# v1_4_button.net
KiCad netlist of a schematic drawn in EAGLE
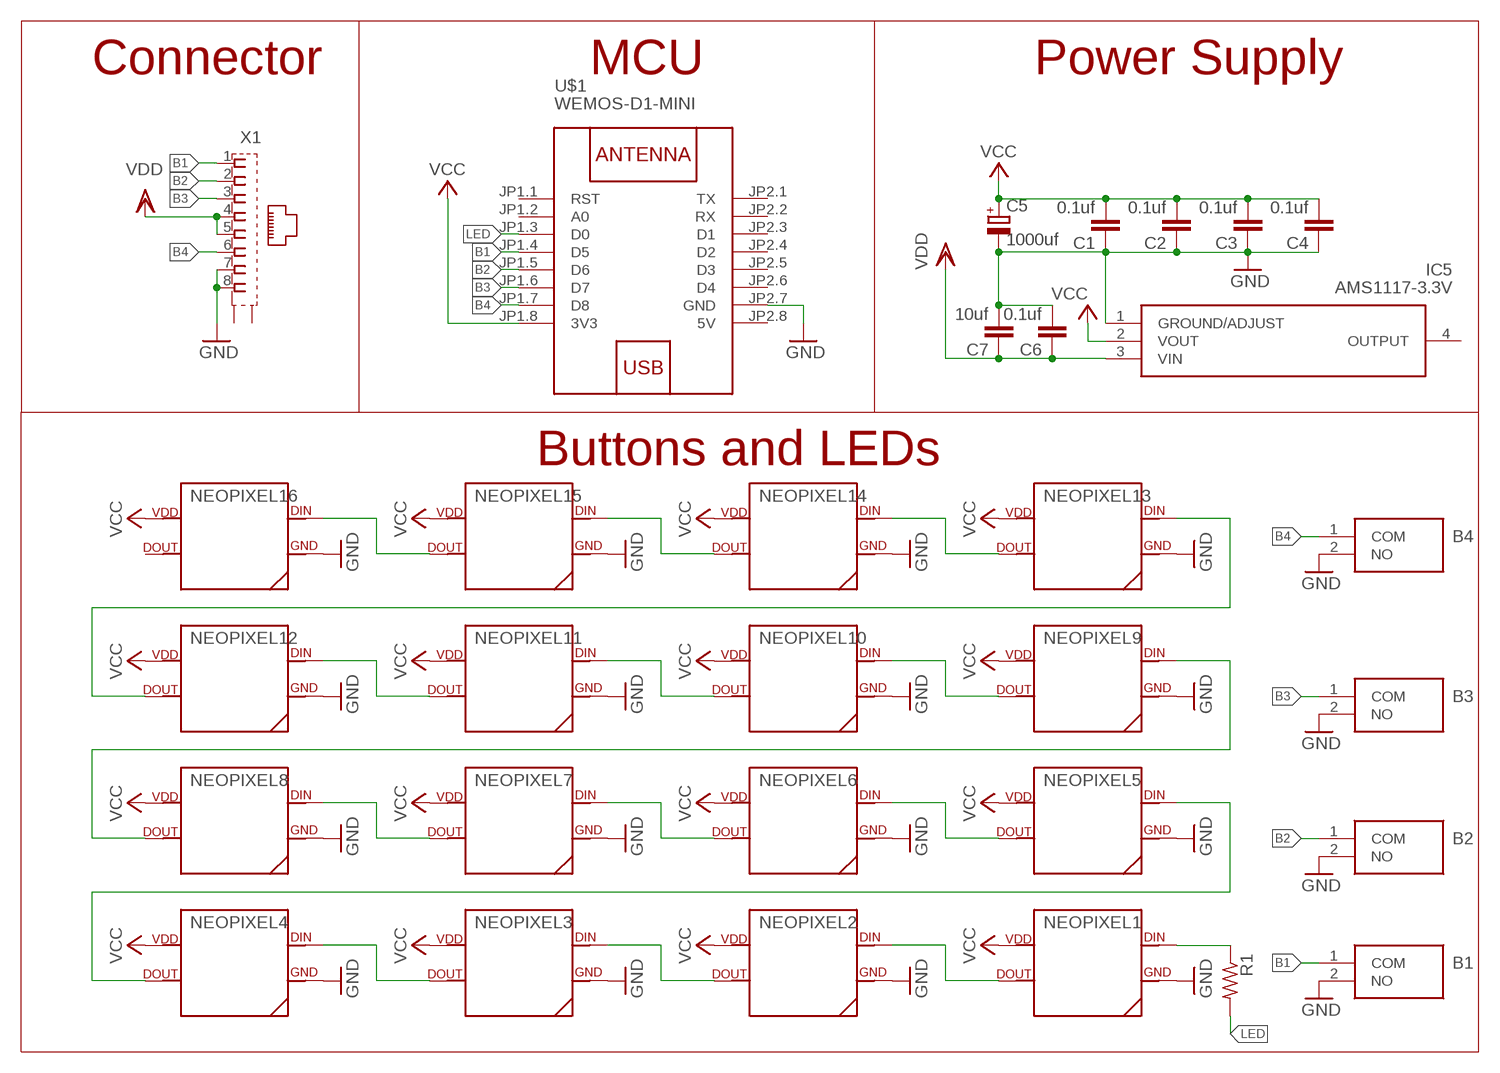
[diagram p0: schematic, sheet 1]

(export (version "E")
  (design (tool "Eeschema 10.0.6"))
  (components
    (comp (ref "B1")
      (value "PTS636_SM25F_SMTR_LFS")
      (footprint "eagle-import:PTS636SM25FSMTRLFS")
      (fields
        (field (name "ARROW_PART_NUMBER") "PTS636 SM25F SMTR LFS")
        (field (name "MOUSER_PART_NUMBER") "611-PTS636SM25FSMTRL")
      )
      (libsource (lib "eagle-import") (part "PTS636_SM25F_SMTR_LFS"))
    )
    (comp (ref "B2")
      (value "PTS636_SM25F_SMTR_LFS")
      (footprint "eagle-import:PTS636SM25FSMTRLFS")
      (fields
        (field (name "ARROW_PART_NUMBER") "PTS636 SM25F SMTR LFS")
        (field (name "MOUSER_PART_NUMBER") "611-PTS636SM25FSMTRL")
      )
      (libsource (lib "eagle-import") (part "PTS636_SM25F_SMTR_LFS"))
    )
    (comp (ref "B3")
      (value "PTS636_SM25F_SMTR_LFS")
      (footprint "eagle-import:PTS636SM25FSMTRLFS")
      (fields
        (field (name "ARROW_PART_NUMBER") "PTS636 SM25F SMTR LFS")
        (field (name "MOUSER_PART_NUMBER") "611-PTS636SM25FSMTRL")
      )
      (libsource (lib "eagle-import") (part "PTS636_SM25F_SMTR_LFS"))
    )
    (comp (ref "B4")
      (value "PTS636_SM25F_SMTR_LFS")
      (footprint "eagle-import:PTS636SM25FSMTRLFS")
      (fields
        (field (name "ARROW_PART_NUMBER") "PTS636 SM25F SMTR LFS")
        (field (name "MOUSER_PART_NUMBER") "611-PTS636SM25FSMTRL")
      )
      (libsource (lib "eagle-import") (part "PTS636_SM25F_SMTR_LFS"))
    )
    (comp (ref "C1")
      (value "0.1uf")
      (footprint "eagle-import:C0603")
      (libsource (lib "eagle-import") (part "C-EUC0603"))
    )
    (comp (ref "C2")
      (value "0.1uf")
      (footprint "eagle-import:C0603")
      (libsource (lib "eagle-import") (part "C-EUC0603"))
    )
    (comp (ref "C3")
      (value "0.1uf")
      (footprint "eagle-import:C0603")
      (libsource (lib "eagle-import") (part "C-EUC0603"))
    )
    (comp (ref "C4")
      (value "0.1uf")
      (footprint "eagle-import:C0603")
      (libsource (lib "eagle-import") (part "C-EUC0603"))
    )
    (comp (ref "C5")
      (value "1000uf")
      (footprint "eagle-import:UD-6,3X7,7_NICHICON")
      (libsource (lib "eagle-import") (part "CPOL-EUUD-6,3X7,7"))
    )
    (comp (ref "C6")
      (value "0.1uf")
      (footprint "eagle-import:C0603")
      (libsource (lib "eagle-import") (part "C-EUC0603"))
    )
    (comp (ref "C7")
      (value "10uf")
      (footprint "eagle-import:C0603")
      (libsource (lib "eagle-import") (part "C-EUC0603"))
    )
    (comp (ref "IC5")
      (value "AMS1117-3.3V")
      (footprint "eagle-import:SOT229P700X180-4N")
      (fields (field (name "MANUFACTURER_PART_NUMBER") "ams1117-3.3v"))
      (libsource (lib "eagle-import") (part "AMS1117-3.3V"))
    )
    (comp (ref "NEOPIXEL1")
      (value "SK6812NEOPIXEL5050")
      (footprint "eagle-import:SK6812")
      (libsource (lib "eagle-import") (part "SK68125050NEOPIXEL"))
    )
    (comp (ref "NEOPIXEL2")
      (value "SK6812NEOPIXEL5050")
      (footprint "eagle-import:SK6812")
      (libsource (lib "eagle-import") (part "SK68125050NEOPIXEL"))
    )
    (comp (ref "NEOPIXEL3")
      (value "SK6812NEOPIXEL5050")
      (footprint "eagle-import:SK6812")
      (libsource (lib "eagle-import") (part "SK68125050NEOPIXEL"))
    )
    (comp (ref "NEOPIXEL4")
      (value "SK6812NEOPIXEL5050")
      (footprint "eagle-import:SK6812")
      (libsource (lib "eagle-import") (part "SK68125050NEOPIXEL"))
    )
    (comp (ref "NEOPIXEL5")
      (value "SK6812NEOPIXEL5050")
      (footprint "eagle-import:SK6812")
      (libsource (lib "eagle-import") (part "SK68125050NEOPIXEL"))
    )
    (comp (ref "NEOPIXEL6")
      (value "SK6812NEOPIXEL5050")
      (footprint "eagle-import:SK6812")
      (libsource (lib "eagle-import") (part "SK68125050NEOPIXEL"))
    )
    (comp (ref "NEOPIXEL7")
      (value "SK6812NEOPIXEL5050")
      (footprint "eagle-import:SK6812")
      (libsource (lib "eagle-import") (part "SK68125050NEOPIXEL"))
    )
    (comp (ref "NEOPIXEL8")
      (value "SK6812NEOPIXEL5050")
      (footprint "eagle-import:SK6812")
      (libsource (lib "eagle-import") (part "SK68125050NEOPIXEL"))
    )
    (comp (ref "NEOPIXEL9")
      (value "SK6812NEOPIXEL5050")
      (footprint "eagle-import:SK6812")
      (libsource (lib "eagle-import") (part "SK68125050NEOPIXEL"))
    )
    (comp (ref "NEOPIXEL10")
      (value "SK6812NEOPIXEL5050")
      (footprint "eagle-import:SK6812")
      (libsource (lib "eagle-import") (part "SK68125050NEOPIXEL"))
    )
    (comp (ref "NEOPIXEL11")
      (value "SK6812NEOPIXEL5050")
      (footprint "eagle-import:SK6812")
      (libsource (lib "eagle-import") (part "SK68125050NEOPIXEL"))
    )
    (comp (ref "NEOPIXEL12")
      (value "SK6812NEOPIXEL5050")
      (footprint "eagle-import:SK6812")
      (libsource (lib "eagle-import") (part "SK68125050NEOPIXEL"))
    )
    (comp (ref "NEOPIXEL13")
      (value "SK6812NEOPIXEL5050")
      (footprint "eagle-import:SK6812")
      (libsource (lib "eagle-import") (part "SK68125050NEOPIXEL"))
    )
    (comp (ref "NEOPIXEL14")
      (value "SK6812NEOPIXEL5050")
      (footprint "eagle-import:SK6812")
      (libsource (lib "eagle-import") (part "SK68125050NEOPIXEL"))
    )
    (comp (ref "NEOPIXEL15")
      (value "SK6812NEOPIXEL5050")
      (footprint "eagle-import:SK6812")
      (libsource (lib "eagle-import") (part "SK68125050NEOPIXEL"))
    )
    (comp (ref "NEOPIXEL16")
      (value "SK6812NEOPIXEL5050")
      (footprint "eagle-import:SK6812")
      (libsource (lib "eagle-import") (part "SK68125050NEOPIXEL"))
    )
    (comp (ref "R1")
      (value "R-US_R0603")
      (footprint "eagle-import:R0603")
      (libsource (lib "eagle-import") (part "R-US_R0603"))
    )
    (comp (ref "U$1")
      (value "WEMOS-D1-MINI")
      (footprint "eagle-import:WEMOS-D1-MINI")
      (libsource (lib "eagle-import") (part "WEMOS-D1-MINI"))
    )
    (comp (ref "X1")
      (value "0446200002")
      (footprint "eagle-import:0446200002")
      (fields (field (name "MF") "MOLEX"))
      (libsource (lib "eagle-import") (part "0446200002"))
    )
  )
  (nets
    (net (code "1") (name "/5V") (class "Default")
      (node (ref "U$1") (pin "JP2.8") (pinfunction "5V_JP2.8") (pintype "power_in"))
    )
    (net (code "2") (name "B1") (class "Default")
      (node (ref "B1") (pin "1") (pinfunction "COM_1") (pintype "bidirectional"))
      (node (ref "U$1") (pin "JP1.4") (pinfunction "D5_JP1.4") (pintype "bidirectional"))
      (node (ref "X1") (pin "1") (pinfunction "1_1") (pintype "passive"))
    )
    (net (code "3") (name "B2") (class "Default")
      (node (ref "B2") (pin "1") (pinfunction "COM_1") (pintype "bidirectional"))
      (node (ref "U$1") (pin "JP1.5") (pinfunction "D6_JP1.5") (pintype "bidirectional"))
      (node (ref "X1") (pin "2") (pinfunction "2_2") (pintype "passive"))
    )
    (net (code "4") (name "B3") (class "Default")
      (node (ref "B3") (pin "1") (pinfunction "COM_1") (pintype "bidirectional"))
      (node (ref "U$1") (pin "JP1.6") (pinfunction "D7_JP1.6") (pintype "bidirectional"))
      (node (ref "X1") (pin "3") (pinfunction "3_3") (pintype "passive"))
    )
    (net (code "5") (name "B4") (class "Default")
      (node (ref "B4") (pin "1") (pinfunction "COM_1") (pintype "bidirectional"))
      (node (ref "U$1") (pin "JP1.7") (pinfunction "D8_JP1.7") (pintype "bidirectional"))
      (node (ref "X1") (pin "6") (pinfunction "6_6") (pintype "passive"))
    )
    (net (code "6") (name "GND") (class "Default")
      (node (ref "B1") (pin "2") (pinfunction "NO_2") (pintype "bidirectional"))
      (node (ref "B2") (pin "2") (pinfunction "NO_2") (pintype "bidirectional"))
      (node (ref "B3") (pin "2") (pinfunction "NO_2") (pintype "bidirectional"))
      (node (ref "B4") (pin "2") (pinfunction "NO_2") (pintype "bidirectional"))
      (node (ref "C1") (pin "1") (pinfunction "1_1") (pintype "passive"))
      (node (ref "C2") (pin "1") (pinfunction "1_1") (pintype "passive"))
      (node (ref "C3") (pin "1") (pinfunction "1_1") (pintype "passive"))
      (node (ref "C4") (pin "1") (pinfunction "1_1") (pintype "passive"))
      (node (ref "C5") (pin "-") (pinfunction "-_-") (pintype "passive"))
      (node (ref "C6") (pin "2") (pinfunction "2_2") (pintype "passive"))
      (node (ref "C7") (pin "2") (pinfunction "2_2") (pintype "passive"))
      (node (ref "IC5") (pin "1") (pinfunction "GROUND/ADJUST_1") (pintype "bidirectional"))
      (node (ref "NEOPIXEL1") (pin "3") (pinfunction "GND_3") (pintype "bidirectional"))
      (node (ref "NEOPIXEL10") (pin "3") (pinfunction "GND_3") (pintype "bidirectional"))
      (node (ref "NEOPIXEL11") (pin "3") (pinfunction "GND_3") (pintype "bidirectional"))
      (node (ref "NEOPIXEL12") (pin "3") (pinfunction "GND_3") (pintype "bidirectional"))
      (node (ref "NEOPIXEL13") (pin "3") (pinfunction "GND_3") (pintype "bidirectional"))
      (node (ref "NEOPIXEL14") (pin "3") (pinfunction "GND_3") (pintype "bidirectional"))
      (node (ref "NEOPIXEL15") (pin "3") (pinfunction "GND_3") (pintype "bidirectional"))
      (node (ref "NEOPIXEL16") (pin "3") (pinfunction "GND_3") (pintype "bidirectional"))
      (node (ref "NEOPIXEL2") (pin "3") (pinfunction "GND_3") (pintype "bidirectional"))
      (node (ref "NEOPIXEL3") (pin "3") (pinfunction "GND_3") (pintype "bidirectional"))
      (node (ref "NEOPIXEL4") (pin "3") (pinfunction "GND_3") (pintype "bidirectional"))
      (node (ref "NEOPIXEL5") (pin "3") (pinfunction "GND_3") (pintype "bidirectional"))
      (node (ref "NEOPIXEL6") (pin "3") (pinfunction "GND_3") (pintype "bidirectional"))
      (node (ref "NEOPIXEL7") (pin "3") (pinfunction "GND_3") (pintype "bidirectional"))
      (node (ref "NEOPIXEL8") (pin "3") (pinfunction "GND_3") (pintype "bidirectional"))
      (node (ref "NEOPIXEL9") (pin "3") (pinfunction "GND_3") (pintype "bidirectional"))
      (node (ref "U$1") (pin "JP2.7") (pinfunction "GND_JP2.7") (pintype "power_in"))
      (node (ref "X1") (pin "7") (pinfunction "7_7") (pintype "passive"))
      (node (ref "X1") (pin "8") (pinfunction "8_8") (pintype "passive"))
    )
    (net (code "7") (name "LED") (class "Default")
      (node (ref "R1") (pin "2") (pinfunction "2_2") (pintype "passive"))
      (node (ref "U$1") (pin "JP1.3") (pinfunction "D0_JP1.3") (pintype "bidirectional"))
    )
    (net (code "8") (name "Net-(NEOPIXEL1-DIN)") (class "Default")
      (node (ref "NEOPIXEL1") (pin "4") (pinfunction "DIN_4") (pintype "bidirectional"))
      (node (ref "R1") (pin "1") (pinfunction "1_1") (pintype "passive"))
    )
    (net (code "9") (name "Net-(NEOPIXEL1-DOUT)") (class "Default")
      (node (ref "NEOPIXEL1") (pin "2") (pinfunction "DOUT_2") (pintype "bidirectional"))
      (node (ref "NEOPIXEL2") (pin "4") (pinfunction "DIN_4") (pintype "bidirectional"))
    )
    (net (code "10") (name "Net-(NEOPIXEL2-DOUT)") (class "Default")
      (node (ref "NEOPIXEL2") (pin "2") (pinfunction "DOUT_2") (pintype "bidirectional"))
      (node (ref "NEOPIXEL3") (pin "4") (pinfunction "DIN_4") (pintype "bidirectional"))
    )
    (net (code "11") (name "Net-(NEOPIXEL3-DOUT)") (class "Default")
      (node (ref "NEOPIXEL3") (pin "2") (pinfunction "DOUT_2") (pintype "bidirectional"))
      (node (ref "NEOPIXEL4") (pin "4") (pinfunction "DIN_4") (pintype "bidirectional"))
    )
    (net (code "12") (name "Net-(NEOPIXEL4-DOUT)") (class "Default")
      (node (ref "NEOPIXEL4") (pin "2") (pinfunction "DOUT_2") (pintype "bidirectional"))
      (node (ref "NEOPIXEL5") (pin "4") (pinfunction "DIN_4") (pintype "bidirectional"))
    )
    (net (code "13") (name "Net-(NEOPIXEL5-DOUT)") (class "Default")
      (node (ref "NEOPIXEL5") (pin "2") (pinfunction "DOUT_2") (pintype "bidirectional"))
      (node (ref "NEOPIXEL6") (pin "4") (pinfunction "DIN_4") (pintype "bidirectional"))
    )
    (net (code "14") (name "Net-(NEOPIXEL6-DOUT)") (class "Default")
      (node (ref "NEOPIXEL6") (pin "2") (pinfunction "DOUT_2") (pintype "bidirectional"))
      (node (ref "NEOPIXEL7") (pin "4") (pinfunction "DIN_4") (pintype "bidirectional"))
    )
    (net (code "15") (name "Net-(NEOPIXEL7-DOUT)") (class "Default")
      (node (ref "NEOPIXEL7") (pin "2") (pinfunction "DOUT_2") (pintype "bidirectional"))
      (node (ref "NEOPIXEL8") (pin "4") (pinfunction "DIN_4") (pintype "bidirectional"))
    )
    (net (code "16") (name "Net-(NEOPIXEL8-DOUT)") (class "Default")
      (node (ref "NEOPIXEL8") (pin "2") (pinfunction "DOUT_2") (pintype "bidirectional"))
      (node (ref "NEOPIXEL9") (pin "4") (pinfunction "DIN_4") (pintype "bidirectional"))
    )
    (net (code "17") (name "Net-(NEOPIXEL10-DIN)") (class "Default")
      (node (ref "NEOPIXEL10") (pin "4") (pinfunction "DIN_4") (pintype "bidirectional"))
      (node (ref "NEOPIXEL9") (pin "2") (pinfunction "DOUT_2") (pintype "bidirectional"))
    )
    (net (code "18") (name "Net-(NEOPIXEL10-DOUT)") (class "Default")
      (node (ref "NEOPIXEL10") (pin "2") (pinfunction "DOUT_2") (pintype "bidirectional"))
      (node (ref "NEOPIXEL11") (pin "4") (pinfunction "DIN_4") (pintype "bidirectional"))
    )
    (net (code "19") (name "Net-(NEOPIXEL11-DOUT)") (class "Default")
      (node (ref "NEOPIXEL11") (pin "2") (pinfunction "DOUT_2") (pintype "bidirectional"))
      (node (ref "NEOPIXEL12") (pin "4") (pinfunction "DIN_4") (pintype "bidirectional"))
    )
    (net (code "20") (name "Net-(NEOPIXEL12-DOUT)") (class "Default")
      (node (ref "NEOPIXEL12") (pin "2") (pinfunction "DOUT_2") (pintype "bidirectional"))
      (node (ref "NEOPIXEL13") (pin "4") (pinfunction "DIN_4") (pintype "bidirectional"))
    )
    (net (code "21") (name "Net-(NEOPIXEL13-DOUT)") (class "Default")
      (node (ref "NEOPIXEL13") (pin "2") (pinfunction "DOUT_2") (pintype "bidirectional"))
      (node (ref "NEOPIXEL14") (pin "4") (pinfunction "DIN_4") (pintype "bidirectional"))
    )
    (net (code "22") (name "Net-(NEOPIXEL14-DOUT)") (class "Default")
      (node (ref "NEOPIXEL14") (pin "2") (pinfunction "DOUT_2") (pintype "bidirectional"))
      (node (ref "NEOPIXEL15") (pin "4") (pinfunction "DIN_4") (pintype "bidirectional"))
    )
    (net (code "23") (name "Net-(NEOPIXEL15-DOUT)") (class "Default")
      (node (ref "NEOPIXEL15") (pin "2") (pinfunction "DOUT_2") (pintype "bidirectional"))
      (node (ref "NEOPIXEL16") (pin "4") (pinfunction "DIN_4") (pintype "bidirectional"))
    )
    (net (code "24") (name "VCC") (class "Default")
      (node (ref "C1") (pin "2") (pinfunction "2_2") (pintype "passive"))
      (node (ref "C2") (pin "2") (pinfunction "2_2") (pintype "passive"))
      (node (ref "C3") (pin "2") (pinfunction "2_2") (pintype "passive"))
      (node (ref "C4") (pin "2") (pinfunction "2_2") (pintype "passive"))
      (node (ref "C5") (pin "+") (pinfunction "+_+") (pintype "passive"))
      (node (ref "IC5") (pin "2") (pinfunction "VOUT_2") (pintype "bidirectional"))
      (node (ref "NEOPIXEL1") (pin "1") (pinfunction "VDD_1") (pintype "bidirectional"))
      (node (ref "NEOPIXEL10") (pin "1") (pinfunction "VDD_1") (pintype "bidirectional"))
      (node (ref "NEOPIXEL11") (pin "1") (pinfunction "VDD_1") (pintype "bidirectional"))
      (node (ref "NEOPIXEL12") (pin "1") (pinfunction "VDD_1") (pintype "bidirectional"))
      (node (ref "NEOPIXEL13") (pin "1") (pinfunction "VDD_1") (pintype "bidirectional"))
      (node (ref "NEOPIXEL14") (pin "1") (pinfunction "VDD_1") (pintype "bidirectional"))
      (node (ref "NEOPIXEL15") (pin "1") (pinfunction "VDD_1") (pintype "bidirectional"))
      (node (ref "NEOPIXEL16") (pin "1") (pinfunction "VDD_1") (pintype "bidirectional"))
      (node (ref "NEOPIXEL2") (pin "1") (pinfunction "VDD_1") (pintype "bidirectional"))
      (node (ref "NEOPIXEL3") (pin "1") (pinfunction "VDD_1") (pintype "bidirectional"))
      (node (ref "NEOPIXEL4") (pin "1") (pinfunction "VDD_1") (pintype "bidirectional"))
      (node (ref "NEOPIXEL5") (pin "1") (pinfunction "VDD_1") (pintype "bidirectional"))
      (node (ref "NEOPIXEL6") (pin "1") (pinfunction "VDD_1") (pintype "bidirectional"))
      (node (ref "NEOPIXEL7") (pin "1") (pinfunction "VDD_1") (pintype "bidirectional"))
      (node (ref "NEOPIXEL8") (pin "1") (pinfunction "VDD_1") (pintype "bidirectional"))
      (node (ref "NEOPIXEL9") (pin "1") (pinfunction "VDD_1") (pintype "bidirectional"))
      (node (ref "U$1") (pin "JP1.8") (pinfunction "3V3_JP1.8") (pintype "power_in"))
    )
    (net (code "25") (name "VDD") (class "Default")
      (node (ref "C6") (pin "1") (pinfunction "1_1") (pintype "passive"))
      (node (ref "C7") (pin "1") (pinfunction "1_1") (pintype "passive"))
      (node (ref "IC5") (pin "3") (pinfunction "VIN_3") (pintype "bidirectional"))
      (node (ref "X1") (pin "4") (pinfunction "4_4") (pintype "passive"))
      (node (ref "X1") (pin "5") (pinfunction "5_5") (pintype "passive"))
    )
    (net (code "26") (name "unconnected-(IC5-OUTPUT-Pad4)") (class "Default")
      (node (ref "IC5") (pin "4") (pinfunction "OUTPUT_4") (pintype "bidirectional"))
    )
    (net (code "27") (name "unconnected-(NEOPIXEL16-DOUT-Pad2)") (class "Default")
      (node (ref "NEOPIXEL16") (pin "2") (pinfunction "DOUT_2") (pintype "bidirectional"))
    )
    (net (code "28") (name "unconnected-(U$1-A0-PadJP1.2)") (class "Default")
      (node (ref "U$1") (pin "JP1.2") (pinfunction "A0_JP1.2") (pintype "bidirectional"))
    )
    (net (code "29") (name "unconnected-(U$1-D1-PadJP2.3)") (class "Default")
      (node (ref "U$1") (pin "JP2.3") (pinfunction "D1_JP2.3") (pintype "bidirectional"))
    )
    (net (code "30") (name "unconnected-(U$1-D2-PadJP2.4)") (class "Default")
      (node (ref "U$1") (pin "JP2.4") (pinfunction "D2_JP2.4") (pintype "bidirectional"))
    )
    (net (code "31") (name "unconnected-(U$1-D3-PadJP2.5)") (class "Default")
      (node (ref "U$1") (pin "JP2.5") (pinfunction "D3_JP2.5") (pintype "bidirectional"))
    )
    (net (code "32") (name "unconnected-(U$1-D4-PadJP2.6)") (class "Default")
      (node (ref "U$1") (pin "JP2.6") (pinfunction "D4_JP2.6") (pintype "bidirectional"))
    )
    (net (code "33") (name "unconnected-(U$1-RST-PadJP1.1)") (class "Default")
      (node (ref "U$1") (pin "JP1.1") (pinfunction "RST_JP1.1") (pintype "bidirectional"))
    )
    (net (code "34") (name "unconnected-(U$1-RX-PadJP2.2)") (class "Default")
      (node (ref "U$1") (pin "JP2.2") (pinfunction "RX_JP2.2") (pintype "bidirectional"))
    )
    (net (code "35") (name "unconnected-(U$1-TX-PadJP2.1)") (class "Default")
      (node (ref "U$1") (pin "JP2.1") (pinfunction "TX_JP2.1") (pintype "bidirectional"))
    )
    (net (code "36") (name "unconnected-(X1-S1-PadS@1)") (class "Default")
      (node (ref "X1") (pin "S@1") (pinfunction "S1_S@1") (pintype "passive"))
    )
    (net (code "37") (name "unconnected-(X1-S2-PadS@2)") (class "Default")
      (node (ref "X1") (pin "S@2") (pinfunction "S2_S@2") (pintype "passive"))
    )
  )
)
